# all_in_a1.net
KiCad netlist of a schematic drawn in Altium Designer
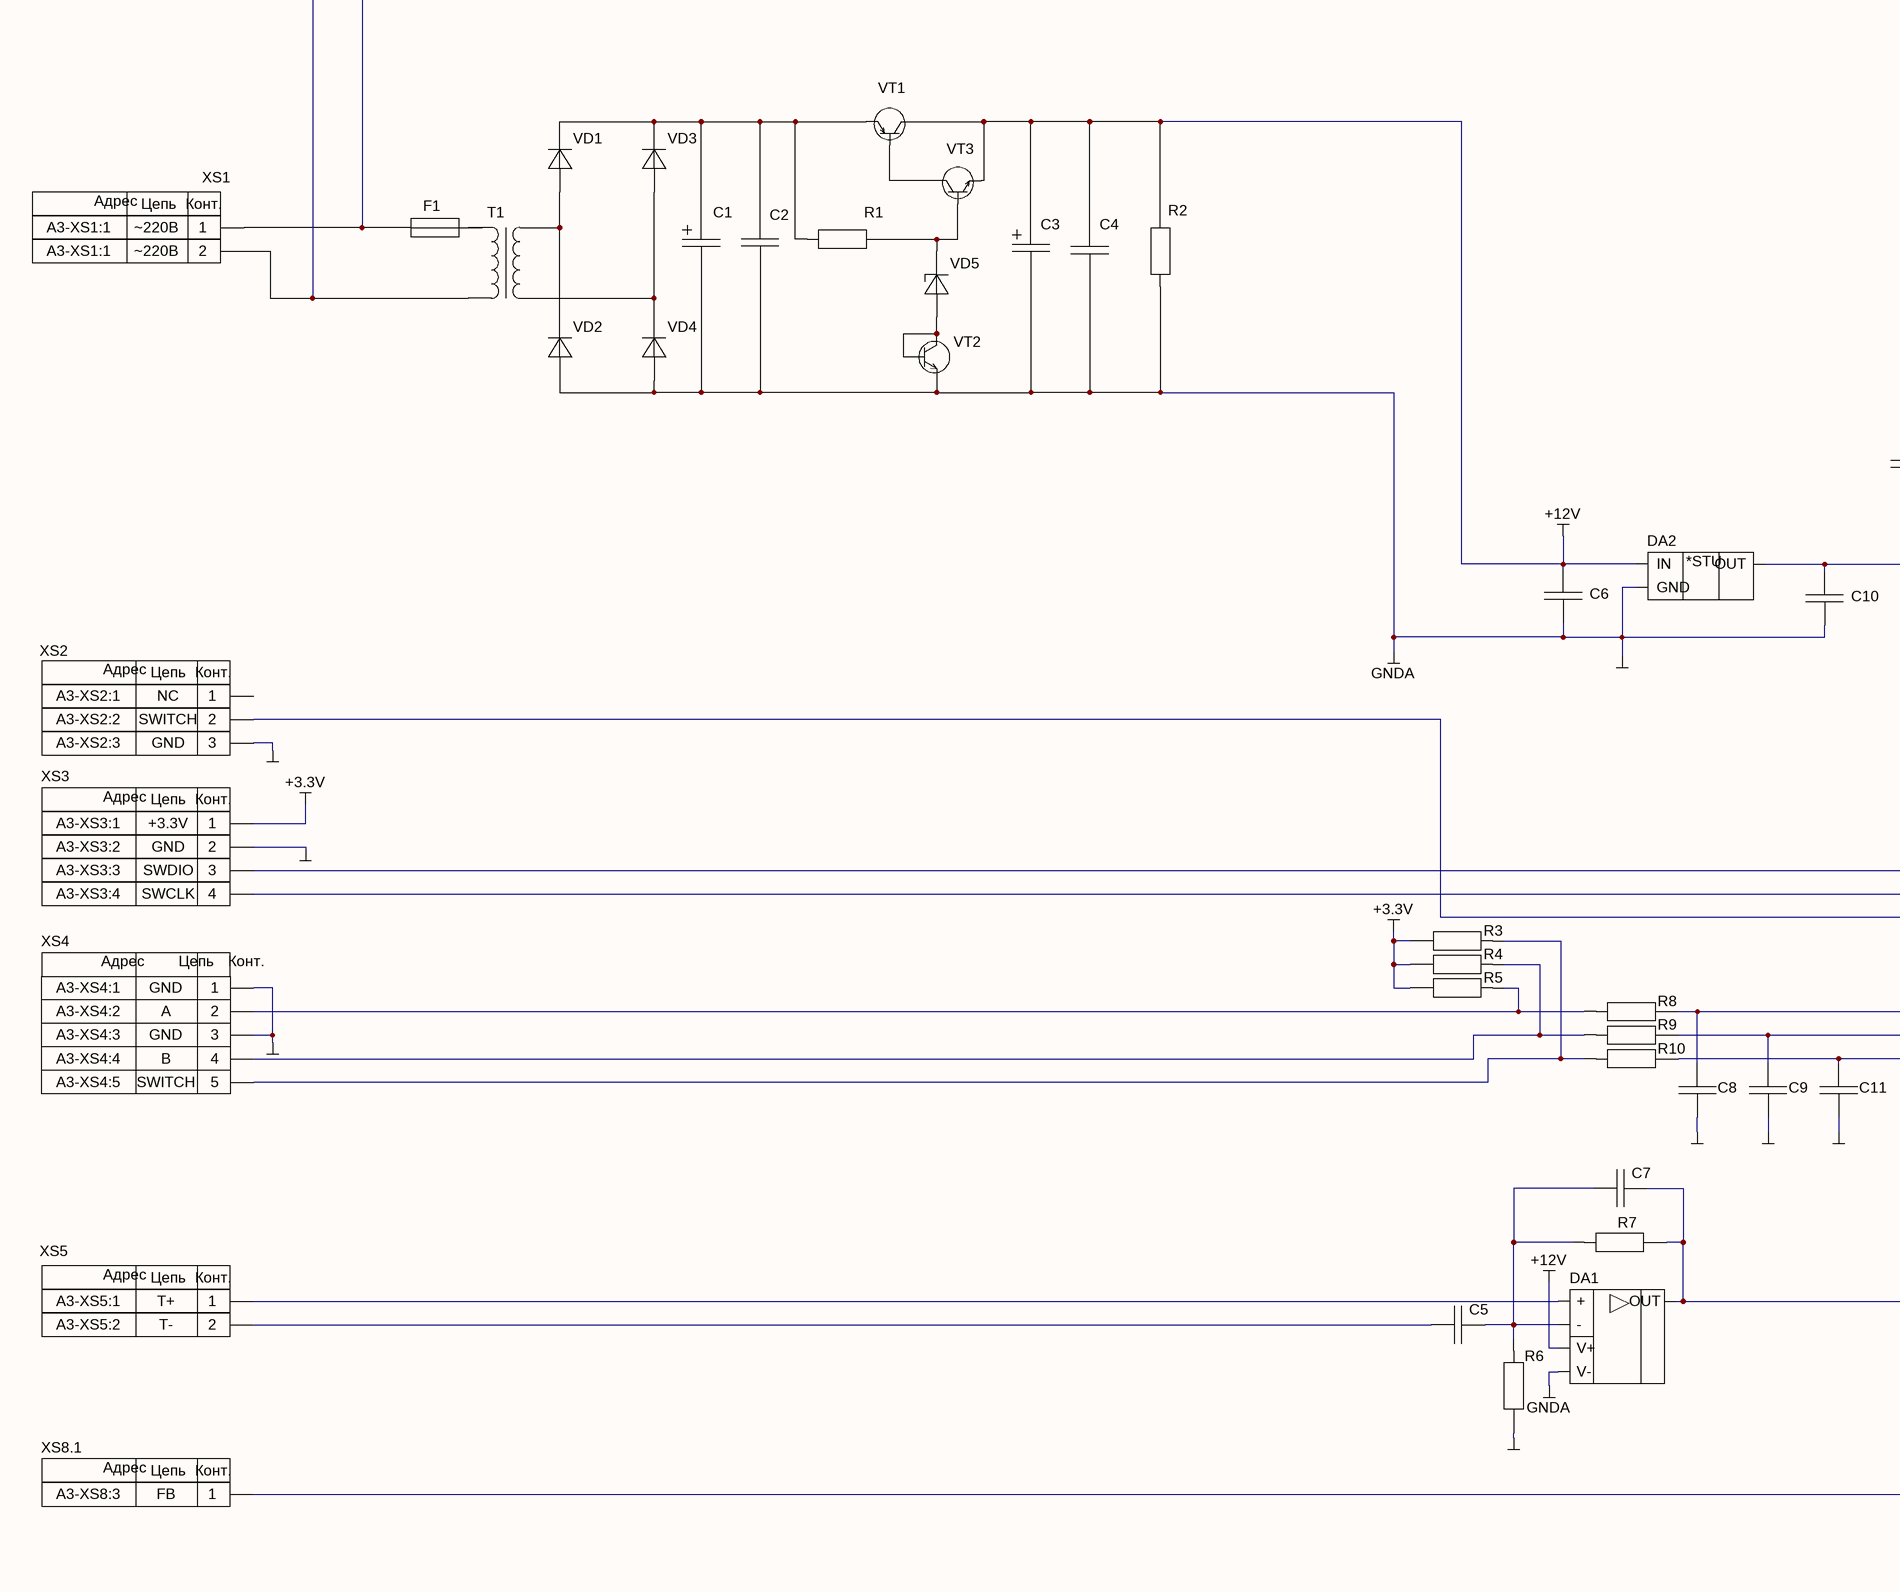
[diagram p0: all_in_a1.SchDoc, left]
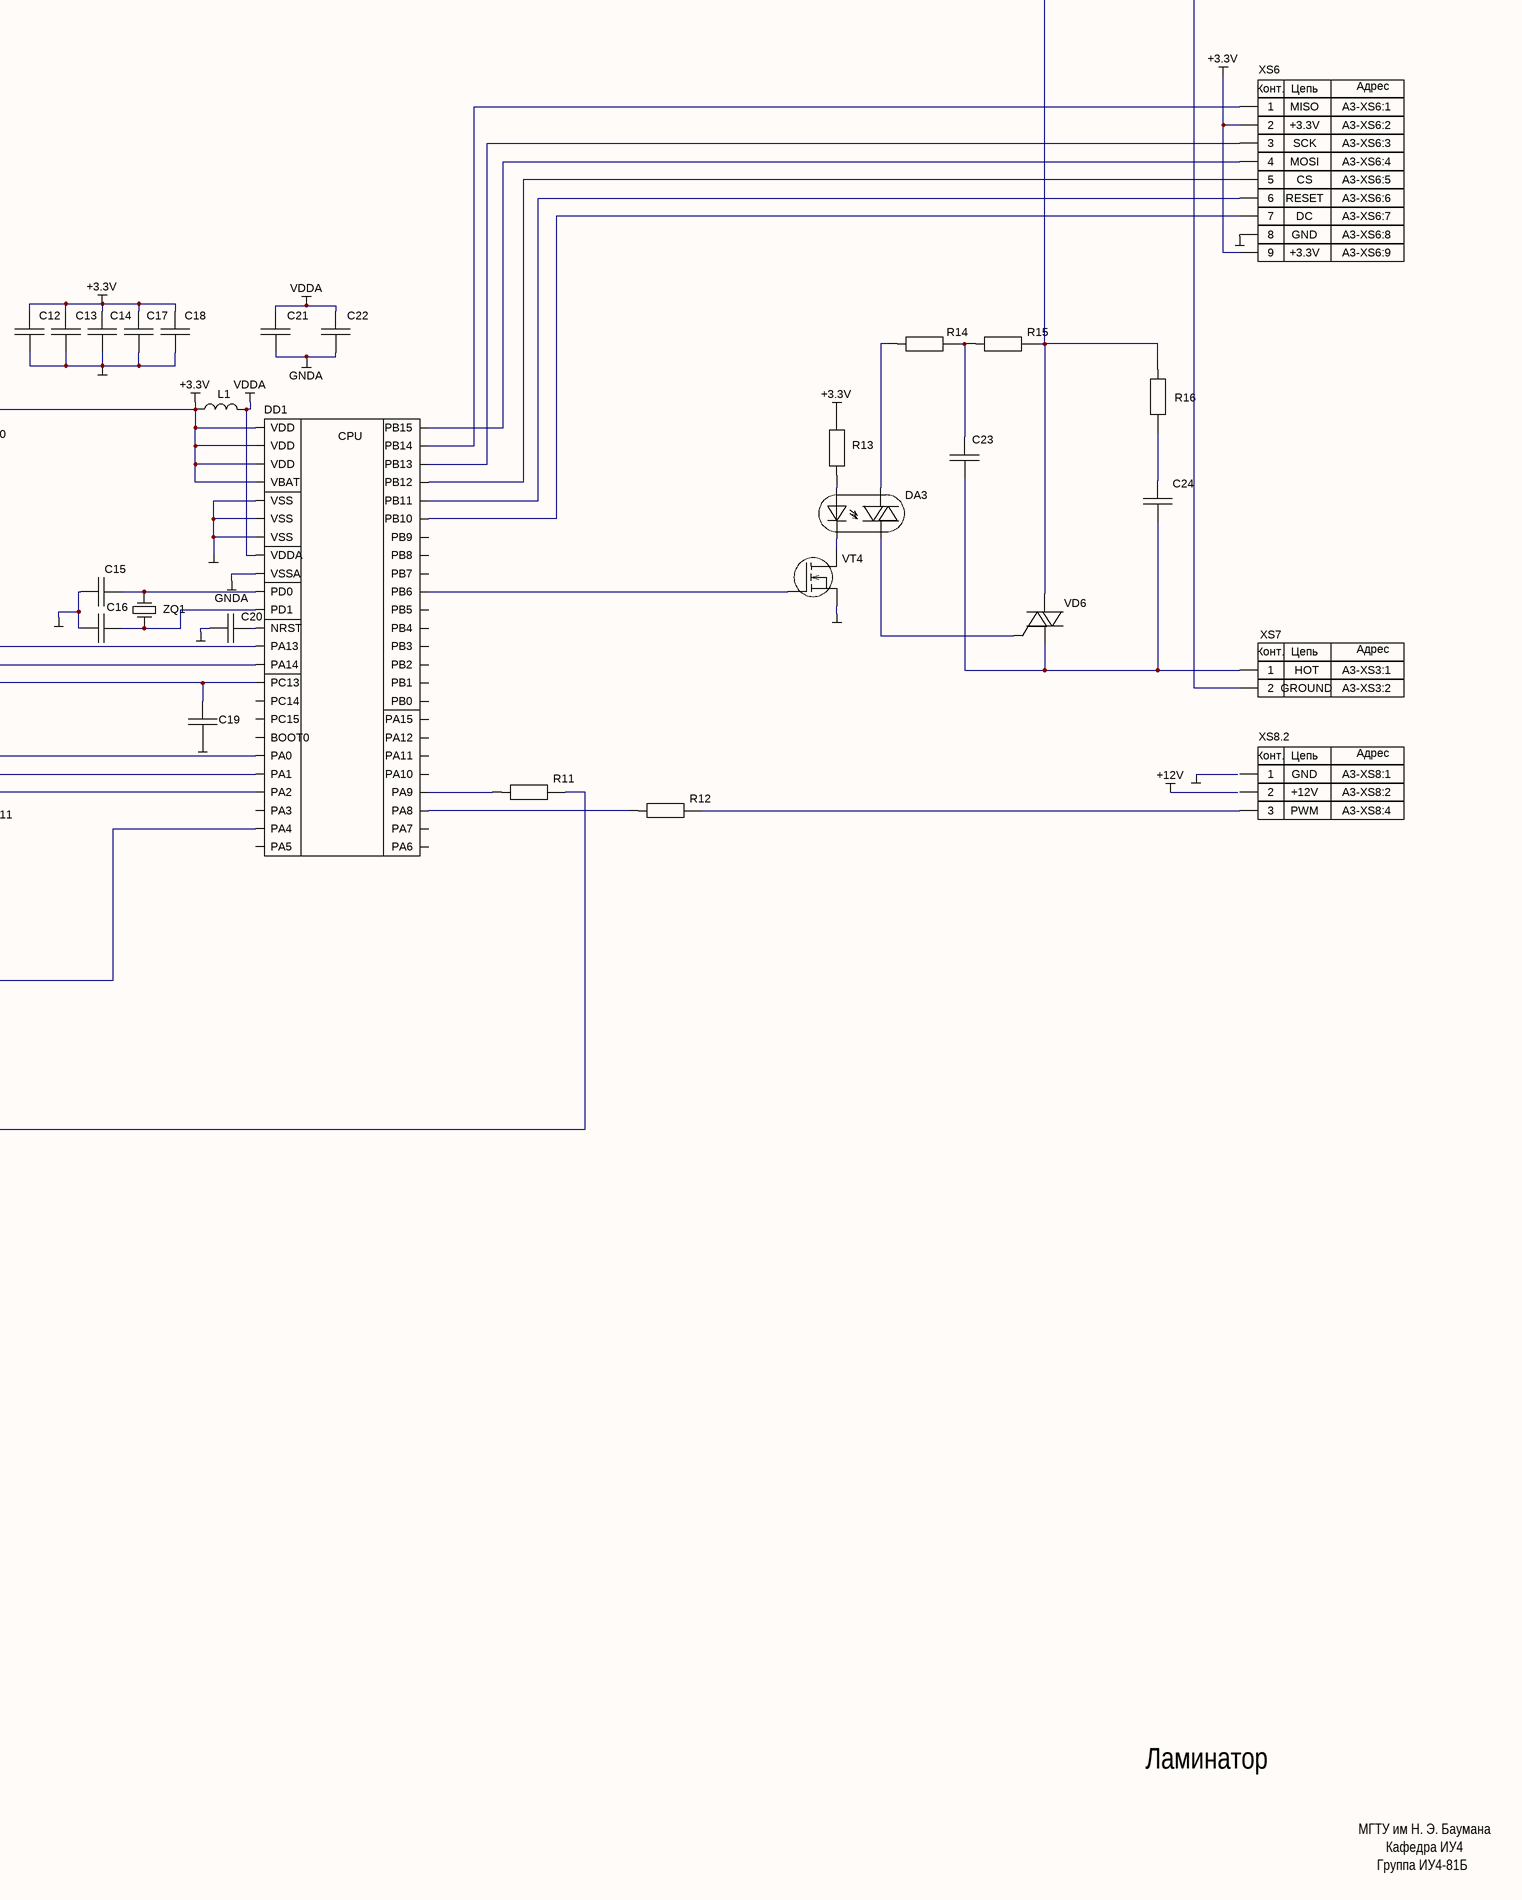
[diagram p1: all_in_a1.SchDoc, right]

(export (version "E")
  (design (tool "Eeschema 10.0.6"))
  (components
    (comp (ref "C1") (value "1000 мкФ") (footprint "CAP: D10C5H20") (libsource (lib "elems") (part "C_pol")))
    (comp (ref "C2") (value "100 нФ") (footprint "CAP: 1206") (libsource (lib "elems") (part "C_const")))
    (comp (ref "C3")
      (value "220 мкФ")
      (footprint "CAP: D6.3C2.5H11")
      (libsource (lib "elems") (part "C_pol"))
    )
    (comp (ref "C4") (value "100нФ") (footprint "CAP: 1206") (libsource (lib "elems") (part "C_const")))
    (comp (ref "C5") (value "100 нФ") (footprint "CAP: 0603") (libsource (lib "elems") (part "C_const")))
    (comp (ref "C6") (value "330 нФ") (footprint "CAP: 0603") (libsource (lib "elems") (part "C_const")))
    (comp (ref "C7") (value "100 нФ") (footprint "CAP: 0603") (libsource (lib "elems") (part "C_const")))
    (comp (ref "C8") (value "100 нФ") (footprint "CAP: 0603") (libsource (lib "elems") (part "C_const")))
    (comp (ref "C9") (value "100 нФ") (footprint "CAP: 0603") (libsource (lib "elems") (part "C_const")))
    (comp (ref "C10") (value "100 нФ") (footprint "CAP: 0603") (libsource (lib "elems") (part "C_const")))
    (comp (ref "C11") (value "100 нФ") (footprint "CAP: 0603") (libsource (lib "elems") (part "C_const")))
    (comp (ref "C12") (value "100 нФ") (footprint "CAP: 0603") (libsource (lib "elems") (part "C_const")))
    (comp (ref "C13") (value "100 нФ") (footprint "CAP: 0603") (libsource (lib "elems") (part "C_const")))
    (comp (ref "C14") (value "100 нФ") (footprint "CAP: 0603") (libsource (lib "elems") (part "C_const")))
    (comp (ref "C15") (value "22 pF") (footprint "CAP: 0603") (libsource (lib "elems") (part "C_const")))
    (comp (ref "C16") (value "22 pF") (footprint "CAP: 0603") (libsource (lib "elems") (part "C_const")))
    (comp (ref "C17") (value "100 нФ") (footprint "CAP: 0603") (libsource (lib "elems") (part "C_const")))
    (comp (ref "C18") (value "4.7 мкФ") (footprint "CAP: 0603") (libsource (lib "elems") (part "C_const")))
    (comp (ref "C19") (value "100 нФ") (footprint "CAP: 0603") (libsource (lib "elems") (part "C_const")))
    (comp (ref "C20") (value "100 нФ") (footprint "CAP: 0603") (libsource (lib "elems") (part "C_const")))
    (comp (ref "C21") (value "10 нФ") (footprint "CAP: 0603") (libsource (lib "elems") (part "C_const")))
    (comp (ref "C22") (value "1 мкФ") (footprint "CAP: 0603") (libsource (lib "elems") (part "C_const")))
    (comp (ref "C23") (value "10 нФ") (footprint "B32652") (libsource (lib "elems") (part "C_const")))
    (comp (ref "C24") (value "10 нФ") (footprint "B32652") (libsource (lib "elems") (part "C_const")))
    (comp (ref "DA1")
      (value "TS321ILT")
      (footprint "SOT23-5")
      (libsource (lib "elems") (part "single_channel_op_amp"))
    )
    (comp (ref "DA2") (value "78xx") (footprint "SOT89") (libsource (lib "elems") (part "78xx")))
    (comp (ref "DA3")
      (value "MOC3020M")
      (footprint "DIP762W48P254L889H508Q6")
      (libsource (lib "elems") (part "opto_triak"))
    )
    (comp (ref "DD1")
      (value "STM32F103C8T6")
      (footprint "48-LQFP")
      (libsource (lib "elems") (part "STM32F103C8T6"))
    )
    (comp (ref "F1")
      (value "0.5 А")
      (footprint "FUSE: 0679H (BelFuse)")
      (libsource (lib "elems") (part "fuse"))
    )
    (comp (ref "L1") (value "10 мкГн") (footprint "IND: 0805") (libsource (lib "elems") (part "L")))
    (comp (ref "R1") (value "330 Ом") (footprint "RES: 1206") (libsource (lib "elems") (part "Res")))
    (comp (ref "R2") (value "1 кОм") (footprint "RES: 1206") (libsource (lib "elems") (part "Res")))
    (comp (ref "R3") (value "10кОм") (footprint "RES: 0603") (libsource (lib "elems") (part "Res")))
    (comp (ref "R4") (value "10кОм") (footprint "RES: 0603") (libsource (lib "elems") (part "Res")))
    (comp (ref "R5") (value "10кОм") (footprint "RES: 0603") (libsource (lib "elems") (part "Res")))
    (comp (ref "R6") (value "1 кОм") (footprint "RES: 1206") (libsource (lib "elems") (part "Res")))
    (comp (ref "R7") (value "47 кОм") (footprint "RES: 1206") (libsource (lib "elems") (part "Res")))
    (comp (ref "R8") (value "10кОм") (footprint "RES: 0603") (libsource (lib "elems") (part "Res")))
    (comp (ref "R9") (value "10кОм") (footprint "RES: 0603") (libsource (lib "elems") (part "Res")))
    (comp (ref "R10") (value "10кОм") (footprint "RES: 0603") (libsource (lib "elems") (part "Res")))
    (comp (ref "R11") (value "220 Ом") (footprint "RES: 1206") (libsource (lib "elems") (part "Res")))
    (comp (ref "R12") (value "220 Ом") (footprint "RES: 1206") (libsource (lib "elems") (part "Res")))
    (comp (ref "R13") (value "Res") (libsource (lib "elems") (part "Res")))
    (comp (ref "R14") (value "Res") (libsource (lib "elems") (part "Res")))
    (comp (ref "R15") (value "Res") (libsource (lib "elems") (part "Res")))
    (comp (ref "R16") (value "Res") (libsource (lib "elems") (part "Res")))
    (comp (ref "T1")
      (value "Trans_1_1")
      (footprint "15v_0.7A_trans")
      (libsource (lib "elems") (part "Trans_1_1"))
    )
    (comp (ref "VD1") (value "1n5400") (footprint "1n5400-1n5408") (libsource (lib "elems") (part "VD")))
    (comp (ref "VD2") (value "1n5400") (footprint "1n5400-1n5408") (libsource (lib "elems") (part "VD")))
    (comp (ref "VD3") (value "1n5400") (footprint "1n5400-1n5408") (libsource (lib "elems") (part "VD")))
    (comp (ref "VD4") (value "1n5400") (footprint "1n5400-1n5408") (libsource (lib "elems") (part "VD")))
    (comp (ref "VD5") (value "1n4742") (footprint "1n4728-1n4764") (libsource (lib "elems") (part "zener")))
    (comp (ref "VD6") (value "BT137-600E") (footprint "TO220") (libsource (lib "elems") (part "triac")))
    (comp (ref "VT1") (value "2SB1132T100Q") (footprint "SOT89") (libsource (lib "elems") (part "pnp")))
    (comp (ref "VT2") (value "2n4401") (footprint "TO-92") (libsource (lib "elems") (part "npn")))
    (comp (ref "VT3") (value "2n4401") (footprint "TO-92") (libsource (lib "elems") (part "npn")))
    (comp (ref "VT4") (value "FDV303N") (footprint "SOT23") (libsource (lib "elems") (part "n-mosfet")))
    (comp (ref "XS1")
      (value "X2")
      (footprint "CON: DG350-3.5-02P")
      (fields
        (field (name "CIRCUIT2") "~220В")
        (field (name "CIRCUIT1") "~220В")
        (field (name "=ADDRESS2") "A3-XS1:1")
        (field (name "=ADDRESS1") "A3-XS1:1")
      )
      (libsource (lib "") (part "X2_1"))
    )
    (comp (ref "XS2")
      (value "X3")
      (footprint "CON: WF-03")
      (fields
        (field (name "CIRCUIT1") "NC")
        (field (name "CIRCUIT2") "SWITCH")
        (field (name "CIRCUIT3") "GND")
        (field (name "=ADDRESS1") "A3-XS2:1")
        (field (name "=ADDRESS2") "A3-XS2:2")
        (field (name "=ADDRESS3") "A3-XS2:3")
      )
      (libsource (lib "elems") (part "X3"))
    )
    (comp (ref "XS3")
      (value "X4")
      (footprint "CON: WF-04")
      (fields
        (field (name "CIRCUIT2") "GND")
        (field (name "CIRCUIT3") "SWDIO")
        (field (name "CIRCUIT1") "+3.3V")
        (field (name "CIRCUIT4") "SWCLK")
        (field (name "=ADDRESS4") "A3-XS3:4")
        (field (name "=ADDRESS3") "A3-XS3:3")
        (field (name "=ADDRESS2") "A3-XS3:2")
        (field (name "=ADDRESS1") "A3-XS3:1")
      )
      (libsource (lib "elems") (part "X4"))
    )
    (comp (ref "XS4")
      (value "X5")
      (footprint "CON: CWF-5")
      (fields
        (field (name "CIRTUIT5") "SWITCH")
        (field (name "CIRCUIT4") "B")
        (field (name "CIRCUIT3") "GND")
        (field (name "CIRCUIT2") "A")
        (field (name "CIRCUIT1") "GND")
        (field (name "=ADDRESS5") "A3-XS4:5")
        (field (name "=ADDRESS4") "A3-XS4:4")
        (field (name "=ADDRESS3") "A3-XS4:3")
        (field (name "=ADDRESS2") "A3-XS4:2")
        (field (name "=ADDRESS1") "A3-XS4:1")
      )
      (libsource (lib "elems") (part "X5"))
    )
    (comp (ref "XS5")
      (value "X2")
      (footprint "CON: WF-02")
      (fields
        (field (name "CIRCUIT2") "T-")
        (field (name "CIRCUIT1") "T+")
        (field (name "=ADDRESS2") "A3-XS5:2")
        (field (name "=ADDRESS1") "A3-XS5:1")
      )
      (libsource (lib "elems") (part "X2"))
    )
    (comp (ref "XS6")
      (value "X9")
      (footprint "CON: IDC-10MS")
      (fields
        (field (name "CIRCTUIT9") "+3.3V")
        (field (name "CIRCTUIT8") "GND")
        (field (name "CIRCTUIT7") "DC")
        (field (name "CIRCTUIT6") "RESET")
        (field (name "CIRCTUIT5") "CS")
        (field (name "CIRCTUIT4") "MOSI")
        (field (name "CIRCTUIT3") "SCK")
        (field (name "CIRCTUIT2") "+3.3V")
        (field (name "CIRCTUIT1") "MISO")
        (field (name "=ADDRESS9") "A3-XS6:9")
        (field (name "=ADDRESS8") "A3-XS6:8")
        (field (name "=ADDRESS7") "A3-XS6:7")
        (field (name "=ADDRESS5") "A3-XS6:5")
        (field (name "=ADDRESS6") "A3-XS6:6")
        (field (name "=ADDRESS4") "A3-XS6:4")
        (field (name "=ADDRESS3") "A3-XS6:3")
        (field (name "=ADDRESS2") "A3-XS6:2")
        (field (name "=ADDRESS1") "A3-XS6:1")
      )
      (libsource (lib "elems") (part "X9"))
    )
    (comp (ref "XS7")
      (value "X2")
      (footprint "CON: WF-02")
      (fields
        (field (name "CIRCUIT2") "GROUND")
        (field (name "CIRCUIT1") "HOT")
        (field (name "=ADDRESS2") "A3-XS3:2")
        (field (name "=ADDRESS1") "A3-XS3:1")
      )
      (libsource (lib "") (part "X2_1"))
    )
    (comp (ref "XS8.1")
      (value "X1")
      (fields (field (name "ADDRESS") "A3-XS8:3") (field (name "CIRCUIT") "FB"))
      (libsource (lib "elems") (part "X1"))
    )
    (comp (ref "XS8.2")
      (value "X3")
      (fields
        (field (name "CIRCUIT1") "GND")
        (field (name "CIRCUIT2") "+12V")
        (field (name "CIRCUIT3") "PWM")
        (field (name "=ADDRESS1") "A3-XS8:1")
        (field (name "=ADDRESS2") "A3-XS8:2")
        (field (name "=ADDRESS3") "A3-XS8:4")
      )
      (libsource (lib "elems") (part "X3"))
    )
    (comp (ref "ZQ1") (value "AT-41CD2-8MHz") (footprint "AT-41CD2") (libsource (lib "elems") (part "ZQ")))
  )
  (nets
    (net (code "1") (name "+3.3V") (class "Default")
      (node (ref "C10") (pin "2") (pinfunction "2_2") (pintype "passive"))
      (node (ref "C12") (pin "2") (pinfunction "2_2") (pintype "passive"))
      (node (ref "C13") (pin "2") (pinfunction "2_2") (pintype "passive"))
      (node (ref "C14") (pin "2") (pinfunction "2_2") (pintype "passive"))
      (node (ref "C17") (pin "2") (pinfunction "2_2") (pintype "passive"))
      (node (ref "C18") (pin "2") (pinfunction "2_2") (pintype "passive"))
      (node (ref "DA2") (pin "2") (pinfunction "OUT_2") (pintype "passive"))
      (node (ref "DD1") (pin "1") (pinfunction "VBAT_1") (pintype "passive"))
      (node (ref "DD1") (pin "24") (pinfunction "VDD_24") (pintype "passive"))
      (node (ref "DD1") (pin "36") (pinfunction "VDD_36") (pintype "passive"))
      (node (ref "DD1") (pin "48") (pinfunction "VDD_48") (pintype "passive"))
      (node (ref "L1") (pin "1") (pinfunction "1_1") (pintype "passive"))
      (node (ref "R13") (pin "2") (pinfunction "6_2") (pintype "passive"))
      (node (ref "R3") (pin "2") (pinfunction "6_2") (pintype "passive"))
      (node (ref "R4") (pin "2") (pinfunction "6_2") (pintype "passive"))
      (node (ref "R5") (pin "2") (pinfunction "6_2") (pintype "passive"))
      (node (ref "XS3") (pin "1") (pinfunction "1_1") (pintype "passive"))
      (node (ref "XS6") (pin "2") (pinfunction "2_2") (pintype "passive"))
      (node (ref "XS6") (pin "9") (pinfunction "9_9") (pintype "passive"))
    )
    (net (code "2") (name "+12V") (class "Default")
      (node (ref "C3") (pin "1") (pinfunction "1_1") (pintype "passive"))
      (node (ref "C4") (pin "1") (pinfunction "1_1") (pintype "passive"))
      (node (ref "C6") (pin "2") (pinfunction "2_2") (pintype "passive"))
      (node (ref "DA1") (pin "5") (pinfunction "V+_5") (pintype "passive"))
      (node (ref "DA2") (pin "1") (pinfunction "IN_1") (pintype "passive"))
      (node (ref "R2") (pin "2") (pinfunction "6_2") (pintype "passive"))
      (node (ref "VT1") (pin "2") (pinfunction "c_2") (pintype "passive"))
      (node (ref "VT3") (pin "3") (pinfunction "e_3") (pintype "passive"))
    )
    (net (code "3") (name "GND") (class "Default")
      (node (ref "C1") (pin "2") (pinfunction "2_2") (pintype "passive"))
      (node (ref "C10") (pin "1") (pinfunction "1_1") (pintype "passive"))
      (node (ref "C11") (pin "1") (pinfunction "1_1") (pintype "passive"))
      (node (ref "C12") (pin "1") (pinfunction "1_1") (pintype "passive"))
      (node (ref "C13") (pin "1") (pinfunction "1_1") (pintype "passive"))
      (node (ref "C14") (pin "1") (pinfunction "1_1") (pintype "passive"))
      (node (ref "C15") (pin "1") (pinfunction "1_1") (pintype "passive"))
      (node (ref "C16") (pin "1") (pinfunction "1_1") (pintype "passive"))
      (node (ref "C17") (pin "1") (pinfunction "1_1") (pintype "passive"))
      (node (ref "C18") (pin "1") (pinfunction "1_1") (pintype "passive"))
      (node (ref "C19") (pin "1") (pinfunction "1_1") (pintype "passive"))
      (node (ref "C2") (pin "1") (pinfunction "1_1") (pintype "passive"))
      (node (ref "C20") (pin "1") (pinfunction "1_1") (pintype "passive"))
      (node (ref "C21") (pin "1") (pinfunction "1_1") (pintype "passive"))
      (node (ref "C22") (pin "1") (pinfunction "1_1") (pintype "passive"))
      (node (ref "C3") (pin "2") (pinfunction "2_2") (pintype "passive"))
      (node (ref "C4") (pin "2") (pinfunction "2_2") (pintype "passive"))
      (node (ref "C6") (pin "1") (pinfunction "1_1") (pintype "passive"))
      (node (ref "C8") (pin "1") (pinfunction "1_1") (pintype "passive"))
      (node (ref "C9") (pin "1") (pinfunction "1_1") (pintype "passive"))
      (node (ref "DA1") (pin "2") (pinfunction "V-_2") (pintype "passive"))
      (node (ref "DA2") (pin "3") (pinfunction "GND_3") (pintype "passive"))
      (node (ref "DD1") (pin "23") (pinfunction "VSS_23") (pintype "passive"))
      (node (ref "DD1") (pin "35") (pinfunction "VSS_35") (pintype "passive"))
      (node (ref "DD1") (pin "47") (pinfunction "VSS_47") (pintype "passive"))
      (node (ref "DD1") (pin "8") (pinfunction "VSSA_8") (pintype "passive"))
      (node (ref "R2") (pin "1") (pinfunction "1_1") (pintype "passive"))
      (node (ref "R6") (pin "2") (pinfunction "6_2") (pintype "passive"))
      (node (ref "VD2") (pin "1") (pinfunction "1_1") (pintype "passive"))
      (node (ref "VD4") (pin "1") (pinfunction "1_1") (pintype "passive"))
      (node (ref "VT2") (pin "3") (pinfunction "e_3") (pintype "passive"))
      (node (ref "VT4") (pin "3") (pinfunction "3_3") (pintype "passive"))
      (node (ref "XS2") (pin "3") (pinfunction "3_3") (pintype "passive"))
      (node (ref "XS3") (pin "2") (pinfunction "2_2") (pintype "passive"))
      (node (ref "XS4") (pin "1") (pinfunction "1_1") (pintype "passive"))
      (node (ref "XS4") (pin "3") (pinfunction "3_3") (pintype "passive"))
      (node (ref "XS6") (pin "8") (pinfunction "8_8") (pintype "passive"))
    )
    (net (code "4") (name "Net-(C5-Pad1)") (class "Default")
      (node (ref "C5") (pin "1") (pinfunction "1_1") (pintype "passive"))
      (node (ref "XS5") (pin "2") (pinfunction "2_2") (pintype "passive"))
    )
    (net (code "5") (name "Net-(C23-Pad1)") (class "Default")
      (node (ref "C23") (pin "1") (pinfunction "1_1") (pintype "passive"))
      (node (ref "C24") (pin "1") (pinfunction "1_1") (pintype "passive"))
      (node (ref "VD6") (pin "1") (pinfunction "1_1") (pintype "passive"))
      (node (ref "XS7") (pin "1") (pinfunction "1_1") (pintype "passive"))
    )
    (net (code "6") (name "Net-(DA1-+)") (class "Default")
      (node (ref "DA1") (pin "1") (pinfunction "+_1") (pintype "passive"))
      (node (ref "XS5") (pin "1") (pinfunction "1_1") (pintype "passive"))
    )
    (net (code "7") (name "Net-(DA1--)") (class "Default")
      (node (ref "C5") (pin "2") (pinfunction "2_2") (pintype "passive"))
      (node (ref "C7") (pin "1") (pinfunction "1_1") (pintype "passive"))
      (node (ref "DA1") (pin "3") (pinfunction "-_3") (pintype "passive"))
      (node (ref "R6") (pin "1") (pinfunction "1_1") (pintype "passive"))
      (node (ref "R7") (pin "1") (pinfunction "1_1") (pintype "passive"))
    )
    (net (code "8") (name "Net-(DA1-OUT)") (class "Default")
      (node (ref "C7") (pin "2") (pinfunction "2_2") (pintype "passive"))
      (node (ref "DA1") (pin "4") (pinfunction "OUT_4") (pintype "passive"))
      (node (ref "DD1") (pin "14") (pinfunction "PA4_14") (pintype "passive"))
      (node (ref "R7") (pin "2") (pinfunction "6_2") (pintype "passive"))
    )
    (net (code "9") (name "Net-(DA3-Pad1)") (class "Default")
      (node (ref "DA3") (pin "1") (pinfunction "1_1") (pintype "passive"))
      (node (ref "R13") (pin "1") (pinfunction "1_1") (pintype "passive"))
    )
    (net (code "10") (name "Net-(DA3-Pad2)") (class "Default")
      (node (ref "DA3") (pin "2") (pinfunction "2_2") (pintype "passive"))
      (node (ref "VT4") (pin "2") (pinfunction "2_2") (pintype "passive"))
    )
    (net (code "11") (name "Net-(DA3-Pad3)") (class "Default")
      (node (ref "DA3") (pin "3") (pinfunction "3_3") (pintype "passive"))
      (node (ref "R14") (pin "1") (pinfunction "1_1") (pintype "passive"))
    )
    (net (code "12") (name "Net-(DA3-Pad4)") (class "Default")
      (node (ref "DA3") (pin "4") (pinfunction "4_4") (pintype "passive"))
      (node (ref "VD6") (pin "3") (pinfunction "3_3") (pintype "passive"))
    )
    (net (code "13") (name "Net-(DD1-NRST)") (class "Default")
      (node (ref "C20") (pin "2") (pinfunction "2_2") (pintype "passive"))
      (node (ref "DD1") (pin "7") (pinfunction "NRST_7") (pintype "passive"))
    )
    (net (code "14") (name "Net-(DD1-PA0)") (class "Default")
      (node (ref "C8") (pin "2") (pinfunction "2_2") (pintype "passive"))
      (node (ref "DD1") (pin "10") (pinfunction "PA0_10") (pintype "passive"))
      (node (ref "R8") (pin "2") (pinfunction "6_2") (pintype "passive"))
    )
    (net (code "15") (name "Net-(DD1-PA1)") (class "Default")
      (node (ref "C9") (pin "2") (pinfunction "2_2") (pintype "passive"))
      (node (ref "DD1") (pin "11") (pinfunction "PA1_11") (pintype "passive"))
      (node (ref "R9") (pin "2") (pinfunction "6_2") (pintype "passive"))
    )
    (net (code "16") (name "Net-(DD1-PA2)") (class "Default")
      (node (ref "C11") (pin "2") (pinfunction "2_2") (pintype "passive"))
      (node (ref "DD1") (pin "12") (pinfunction "PA2_12") (pintype "passive"))
      (node (ref "R10") (pin "2") (pinfunction "6_2") (pintype "passive"))
    )
    (net (code "17") (name "Net-(DD1-PA8)") (class "Default")
      (node (ref "DD1") (pin "29") (pinfunction "PA8_29") (pintype "passive"))
      (node (ref "R12") (pin "1") (pinfunction "1_1") (pintype "passive"))
    )
    (net (code "18") (name "Net-(DD1-PA9)") (class "Default")
      (node (ref "DD1") (pin "30") (pinfunction "PA9_30") (pintype "passive"))
      (node (ref "R11") (pin "1") (pinfunction "1_1") (pintype "passive"))
    )
    (net (code "19") (name "Net-(DD1-PA13)") (class "Default")
      (node (ref "DD1") (pin "34") (pinfunction "PA13_34") (pintype "passive"))
      (node (ref "XS3") (pin "3") (pinfunction "3_3") (pintype "passive"))
    )
    (net (code "20") (name "Net-(DD1-PA14)") (class "Default")
      (node (ref "DD1") (pin "37") (pinfunction "PA14_37") (pintype "passive"))
      (node (ref "XS3") (pin "4") (pinfunction "4_4") (pintype "passive"))
    )
    (net (code "21") (name "Net-(DD1-PB6)") (class "Default")
      (node (ref "DD1") (pin "42") (pinfunction "PB6_42") (pintype "passive"))
      (node (ref "VT4") (pin "1") (pinfunction "1_1") (pintype "passive"))
    )
    (net (code "22") (name "Net-(DD1-PB10)") (class "Default")
      (node (ref "DD1") (pin "21") (pinfunction "PB10_21") (pintype "passive"))
      (node (ref "XS6") (pin "7") (pinfunction "7_7") (pintype "passive"))
    )
    (net (code "23") (name "Net-(DD1-PB11)") (class "Default")
      (node (ref "DD1") (pin "22") (pinfunction "PB11_22") (pintype "passive"))
      (node (ref "XS6") (pin "6") (pinfunction "6_6") (pintype "passive"))
    )
    (net (code "24") (name "Net-(DD1-PB12)") (class "Default")
      (node (ref "DD1") (pin "25") (pinfunction "PB12_25") (pintype "passive"))
      (node (ref "XS6") (pin "5") (pinfunction "5_5") (pintype "passive"))
    )
    (net (code "25") (name "Net-(DD1-PB13)") (class "Default")
      (node (ref "DD1") (pin "26") (pinfunction "PB13_26") (pintype "passive"))
      (node (ref "XS6") (pin "3") (pinfunction "3_3") (pintype "passive"))
    )
    (net (code "26") (name "Net-(DD1-PB14)") (class "Default")
      (node (ref "DD1") (pin "27") (pinfunction "PB14_27") (pintype "passive"))
      (node (ref "XS6") (pin "1") (pinfunction "1_1") (pintype "passive"))
    )
    (net (code "27") (name "Net-(DD1-PB15)") (class "Default")
      (node (ref "DD1") (pin "28") (pinfunction "PB15_28") (pintype "passive"))
      (node (ref "XS6") (pin "4") (pinfunction "4_4") (pintype "passive"))
    )
    (net (code "28") (name "Net-(DD1-PC13)") (class "Default")
      (node (ref "C19") (pin "2") (pinfunction "2_2") (pintype "passive"))
      (node (ref "DD1") (pin "2") (pinfunction "PC13_2") (pintype "passive"))
      (node (ref "XS2") (pin "2") (pinfunction "2_2") (pintype "passive"))
    )
    (net (code "29") (name "Net-(DD1-PD0)") (class "Default")
      (node (ref "C15") (pin "2") (pinfunction "2_2") (pintype "passive"))
      (node (ref "DD1") (pin "5") (pinfunction "PD0_5") (pintype "passive"))
      (node (ref "ZQ1") (pin "1") (pinfunction "1_1") (pintype "passive"))
    )
    (net (code "30") (name "Net-(DD1-PD1)") (class "Default")
      (node (ref "C16") (pin "2") (pinfunction "2_2") (pintype "passive"))
      (node (ref "DD1") (pin "6") (pinfunction "PD1_6") (pintype "passive"))
      (node (ref "ZQ1") (pin "2") (pinfunction "2_2") (pintype "passive"))
    )
    (net (code "31") (name "Net-(F1-Pad2)") (class "Default")
      (node (ref "F1") (pin "2") (pinfunction "2_2") (pintype "passive"))
      (node (ref "T1") (pin "1") (pinfunction "1_1") (pintype "passive"))
    )
    (net (code "32") (name "Net-(R1-6)") (class "Default")
      (node (ref "R1") (pin "2") (pinfunction "6_2") (pintype "passive"))
      (node (ref "VD5") (pin "2") (pinfunction "2_2") (pintype "passive"))
      (node (ref "VT3") (pin "1") (pinfunction "b_1") (pintype "passive"))
    )
    (net (code "33") (name "Net-(R4-Pad1)") (class "Default")
      (node (ref "R4") (pin "1") (pinfunction "1_1") (pintype "passive"))
      (node (ref "R9") (pin "1") (pinfunction "1_1") (pintype "passive"))
      (node (ref "XS4") (pin "4") (pinfunction "4_4") (pintype "passive"))
    )
    (net (code "34") (name "Net-(R5-Pad1)") (class "Default")
      (node (ref "R5") (pin "1") (pinfunction "1_1") (pintype "passive"))
      (node (ref "R8") (pin "1") (pinfunction "1_1") (pintype "passive"))
      (node (ref "XS4") (pin "2") (pinfunction "2_2") (pintype "passive"))
    )
    (net (code "35") (name "Net-(R10-Pad1)") (class "Default")
      (node (ref "R10") (pin "1") (pinfunction "1_1") (pintype "passive"))
      (node (ref "R3") (pin "1") (pinfunction "1_1") (pintype "passive"))
      (node (ref "XS4") (pin "5") (pinfunction "5_5") (pintype "passive"))
    )
    (net (code "36") (name "Net-(R11-6)") (class "Default")
      (node (ref "R11") (pin "2") (pinfunction "6_2") (pintype "passive"))
      (node (ref "XS8.1") (pin "1") (pinfunction "1_1") (pintype "passive"))
    )
    (net (code "37") (name "Net-(R12-6)") (class "Default")
      (node (ref "R12") (pin "2") (pinfunction "6_2") (pintype "passive"))
      (node (ref "XS8.2") (pin "3") (pinfunction "3_3") (pintype "passive"))
    )
    (net (code "38") (name "Net-(R14-6)") (class "Default")
      (node (ref "C23") (pin "2") (pinfunction "2_2") (pintype "passive"))
      (node (ref "R14") (pin "2") (pinfunction "6_2") (pintype "passive"))
      (node (ref "R15") (pin "1") (pinfunction "1_1") (pintype "passive"))
    )
    (net (code "39") (name "Net-(R15-6)") (class "Default")
      (node (ref "F1") (pin "1") (pinfunction "1_1") (pintype "passive"))
      (node (ref "R15") (pin "2") (pinfunction "6_2") (pintype "passive"))
      (node (ref "R16") (pin "1") (pinfunction "1_1") (pintype "passive"))
      (node (ref "VD6") (pin "2") (pinfunction "2_2") (pintype "passive"))
      (node (ref "XS1") (pin "1") (pinfunction "1_1") (pintype "passive"))
    )
    (net (code "40") (name "Net-(R16-6)") (class "Default")
      (node (ref "C24") (pin "2") (pinfunction "2_2") (pintype "passive"))
      (node (ref "R16") (pin "2") (pinfunction "6_2") (pintype "passive"))
    )
    (net (code "41") (name "Net-(T1-Pad2)") (class "Default")
      (node (ref "T1") (pin "2") (pinfunction "2_2") (pintype "passive"))
      (node (ref "XS1") (pin "2") (pinfunction "2_2") (pintype "passive"))
      (node (ref "XS7") (pin "2") (pinfunction "2_2") (pintype "passive"))
    )
    (net (code "42") (name "Net-(T1-Pad3)") (class "Default")
      (node (ref "T1") (pin "3") (pinfunction "3_3") (pintype "passive"))
      (node (ref "VD1") (pin "1") (pinfunction "1_1") (pintype "passive"))
      (node (ref "VD2") (pin "2") (pinfunction "2_2") (pintype "passive"))
    )
    (net (code "43") (name "Net-(T1-Pad4)") (class "Default")
      (node (ref "T1") (pin "4") (pinfunction "4_4") (pintype "passive"))
      (node (ref "VD3") (pin "1") (pinfunction "1_1") (pintype "passive"))
      (node (ref "VD4") (pin "2") (pinfunction "2_2") (pintype "passive"))
    )
    (net (code "44") (name "Net-(VT1-b)") (class "Default")
      (node (ref "VT1") (pin "1") (pinfunction "b_1") (pintype "passive"))
      (node (ref "VT3") (pin "2") (pinfunction "c_2") (pintype "passive"))
    )
    (net (code "45") (name "Net-(VT1-e)") (class "Default")
      (node (ref "C1") (pin "1") (pinfunction "1_1") (pintype "passive"))
      (node (ref "C2") (pin "2") (pinfunction "2_2") (pintype "passive"))
      (node (ref "R1") (pin "1") (pinfunction "1_1") (pintype "passive"))
      (node (ref "VD1") (pin "2") (pinfunction "2_2") (pintype "passive"))
      (node (ref "VD3") (pin "2") (pinfunction "2_2") (pintype "passive"))
      (node (ref "VT1") (pin "3") (pinfunction "e_3") (pintype "passive"))
    )
    (net (code "46") (name "Net-(VT2-b)") (class "Default")
      (node (ref "VD5") (pin "1") (pinfunction "1_1") (pintype "passive"))
      (node (ref "VT2") (pin "1") (pinfunction "b_1") (pintype "passive"))
      (node (ref "VT2") (pin "2") (pinfunction "c_2") (pintype "passive"))
    )
    (net (code "47") (name "VDDA") (class "Default")
      (node (ref "C21") (pin "2") (pinfunction "2_2") (pintype "passive"))
      (node (ref "C22") (pin "2") (pinfunction "2_2") (pintype "passive"))
      (node (ref "DD1") (pin "9") (pinfunction "VDDA_9") (pintype "passive"))
      (node (ref "L1") (pin "2") (pinfunction "2_2") (pintype "passive"))
    )
    (net (code "48") (name "unconnected-(DD1-BOOT0-Pad44)") (class "Default")
      (node (ref "DD1") (pin "44") (pinfunction "BOOT0_44") (pintype "passive"))
    )
    (net (code "49") (name "unconnected-(DD1-PA3-Pad13)") (class "Default")
      (node (ref "DD1") (pin "13") (pinfunction "PA3_13") (pintype "passive"))
    )
    (net (code "50") (name "unconnected-(DD1-PA5-Pad15)") (class "Default")
      (node (ref "DD1") (pin "15") (pinfunction "PA5_15") (pintype "passive"))
    )
    (net (code "51") (name "unconnected-(DD1-PA6-Pad16)") (class "Default")
      (node (ref "DD1") (pin "16") (pinfunction "PA6_16") (pintype "passive"))
    )
    (net (code "52") (name "unconnected-(DD1-PA7-Pad17)") (class "Default")
      (node (ref "DD1") (pin "17") (pinfunction "PA7_17") (pintype "passive"))
    )
    (net (code "53") (name "unconnected-(DD1-PA10-Pad31)") (class "Default")
      (node (ref "DD1") (pin "31") (pinfunction "PA10_31") (pintype "passive"))
    )
    (net (code "54") (name "unconnected-(DD1-PA11-Pad32)") (class "Default")
      (node (ref "DD1") (pin "32") (pinfunction "PA11_32") (pintype "passive"))
    )
    (net (code "55") (name "unconnected-(DD1-PA12-Pad33)") (class "Default")
      (node (ref "DD1") (pin "33") (pinfunction "PA12_33") (pintype "passive"))
    )
    (net (code "56") (name "unconnected-(DD1-PA15-Pad38)") (class "Default")
      (node (ref "DD1") (pin "38") (pinfunction "PA15_38") (pintype "passive"))
    )
    (net (code "57") (name "unconnected-(DD1-PB0-Pad18)") (class "Default")
      (node (ref "DD1") (pin "18") (pinfunction "PB0_18") (pintype "passive"))
    )
    (net (code "58") (name "unconnected-(DD1-PB1-Pad19)") (class "Default")
      (node (ref "DD1") (pin "19") (pinfunction "PB1_19") (pintype "passive"))
    )
    (net (code "59") (name "unconnected-(DD1-PB2-Pad20)") (class "Default")
      (node (ref "DD1") (pin "20") (pinfunction "PB2_20") (pintype "passive"))
    )
    (net (code "60") (name "unconnected-(DD1-PB3-Pad39)") (class "Default")
      (node (ref "DD1") (pin "39") (pinfunction "PB3_39") (pintype "passive"))
    )
    (net (code "61") (name "unconnected-(DD1-PB4-Pad40)") (class "Default")
      (node (ref "DD1") (pin "40") (pinfunction "PB4_40") (pintype "passive"))
    )
    (net (code "62") (name "unconnected-(DD1-PB5-Pad41)") (class "Default")
      (node (ref "DD1") (pin "41") (pinfunction "PB5_41") (pintype "passive"))
    )
    (net (code "63") (name "unconnected-(DD1-PB7-Pad43)") (class "Default")
      (node (ref "DD1") (pin "43") (pinfunction "PB7_43") (pintype "passive"))
    )
    (net (code "64") (name "unconnected-(DD1-PB8-Pad45)") (class "Default")
      (node (ref "DD1") (pin "45") (pinfunction "PB8_45") (pintype "passive"))
    )
    (net (code "65") (name "unconnected-(DD1-PB9-Pad46)") (class "Default")
      (node (ref "DD1") (pin "46") (pinfunction "PB9_46") (pintype "passive"))
    )
    (net (code "66") (name "unconnected-(DD1-PC14-Pad3)") (class "Default")
      (node (ref "DD1") (pin "3") (pinfunction "PC14_3") (pintype "passive"))
    )
    (net (code "67") (name "unconnected-(DD1-PC15-Pad4)") (class "Default")
      (node (ref "DD1") (pin "4") (pinfunction "PC15_4") (pintype "passive"))
    )
    (net (code "68") (name "unconnected-(XS2-Pad1)") (class "Default")
      (node (ref "XS2") (pin "1") (pinfunction "1_1") (pintype "passive"))
    )
    (net (code "69") (name "unconnected-(XS8.2-Pad1)") (class "Default")
      (node (ref "XS8.2") (pin "1") (pinfunction "1_1") (pintype "passive"))
    )
    (net (code "70") (name "unconnected-(XS8.2-Pad2)") (class "Default")
      (node (ref "XS8.2") (pin "2") (pinfunction "2_2") (pintype "passive"))
    )
  )
)
